# pc_max86150_breakout_qwiic_v1_3.net
KiCad netlist of a schematic drawn in EAGLE
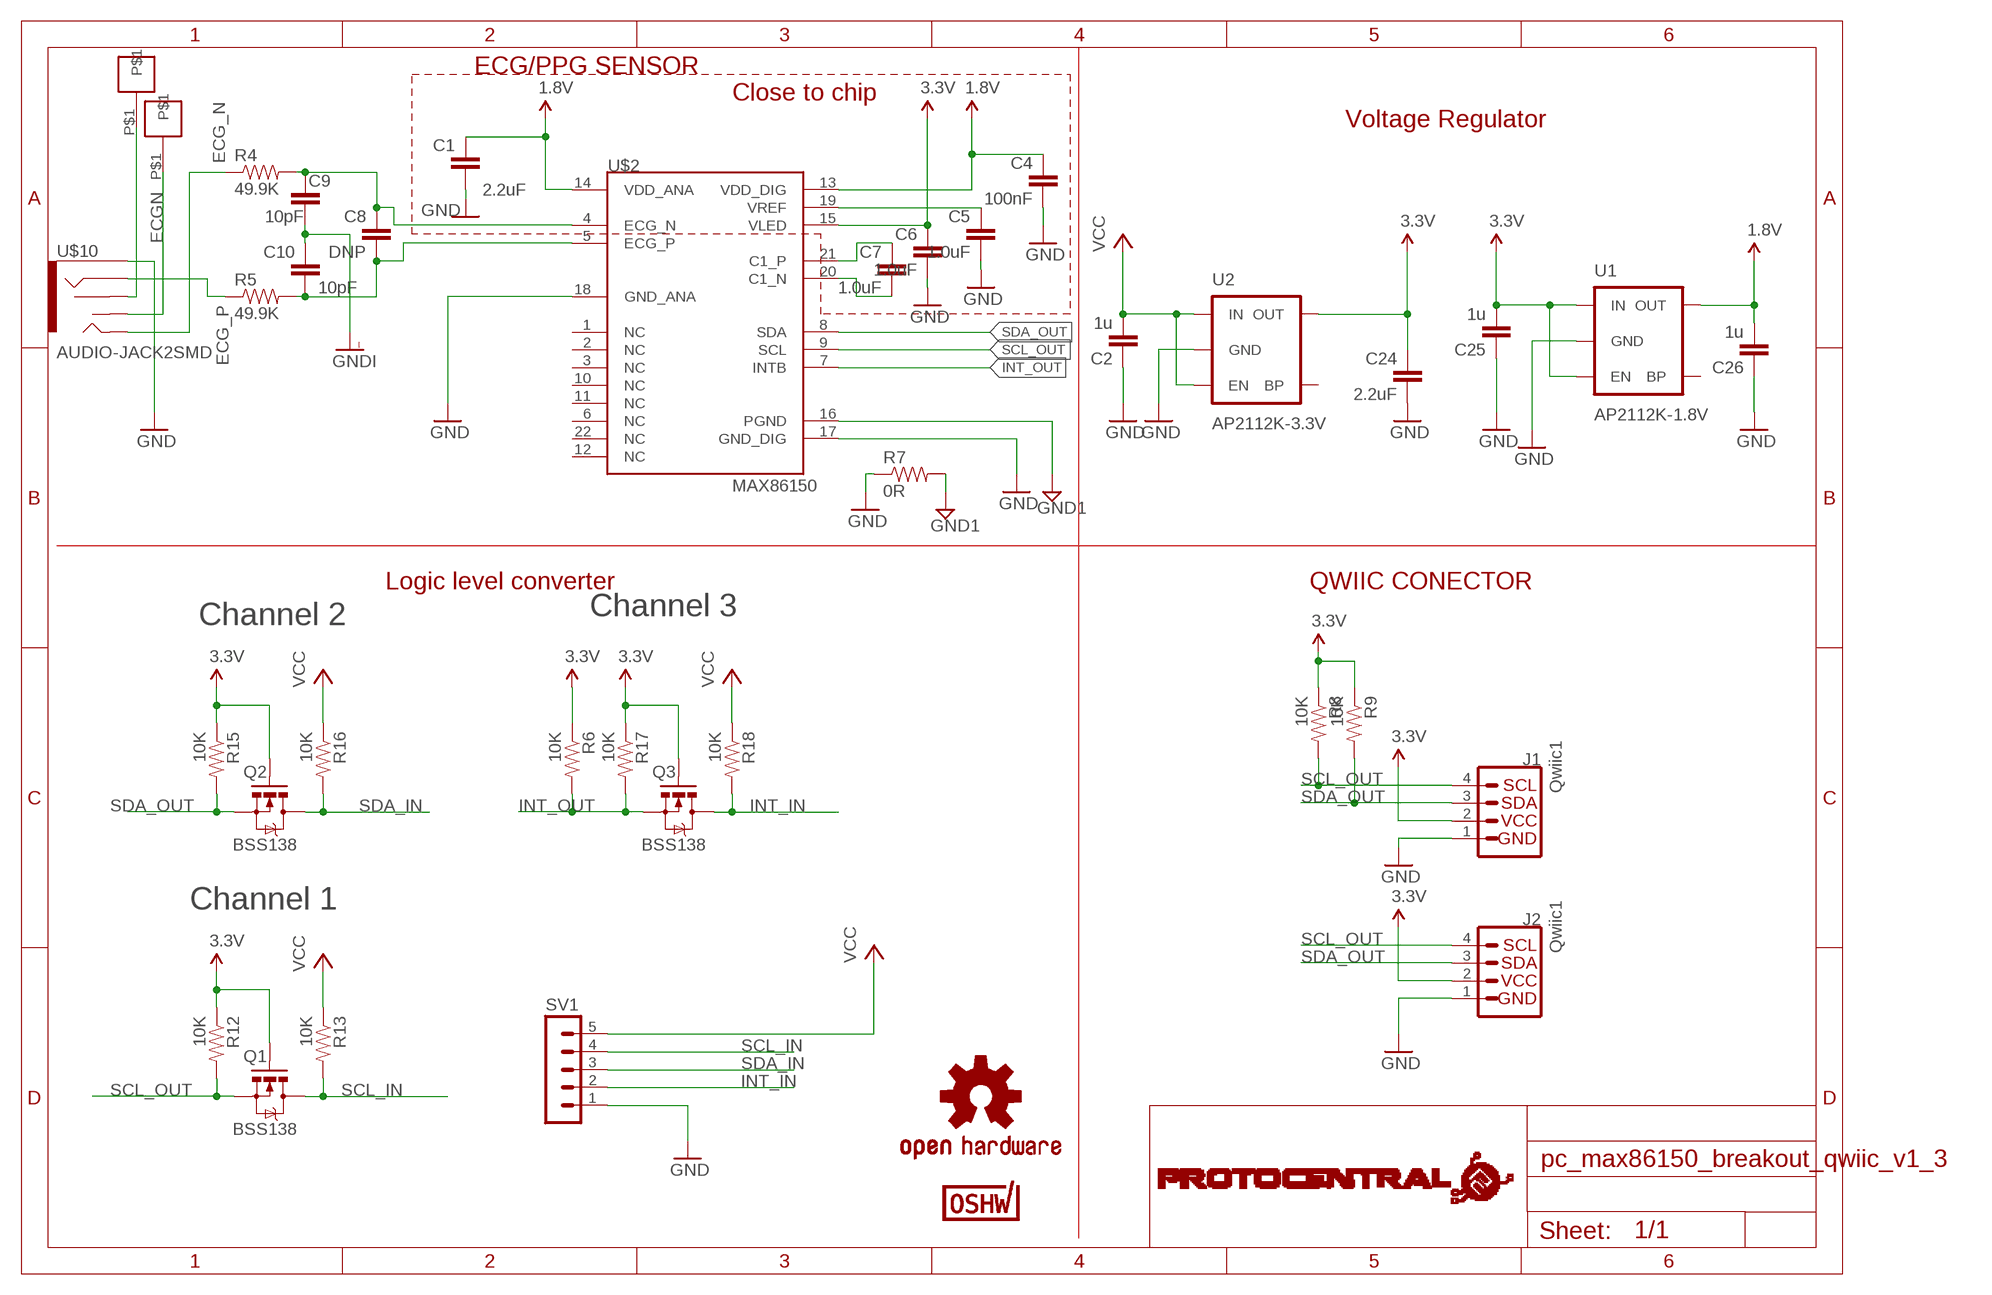
[diagram p0: schematic, sheet 1]

(export (version "E")
  (design (tool "Eeschema 10.0.6"))
  (components
    (comp (ref "C1")
      (value "2.2uF")
      (footprint "eagle-import:0402")
      (libsource (lib "eagle-import") (part "1.0UF-0402-16V-10%"))
    )
    (comp (ref "C2")
      (value "1u")
      (footprint "eagle-import:C0402")
      (libsource (lib "eagle-import") (part "C-EUC0402"))
    )
    (comp (ref "C4")
      (value "100nF")
      (footprint "eagle-import:0402")
      (libsource (lib "eagle-import") (part "1.0UF-0402-16V-10%"))
    )
    (comp (ref "C5")
      (value "1.0uF")
      (footprint "eagle-import:0402")
      (libsource (lib "eagle-import") (part "1.0UF-0402-16V-10%"))
    )
    (comp (ref "C6")
      (value "1.0uF")
      (footprint "eagle-import:0402")
      (libsource (lib "eagle-import") (part "1.0UF-0402-16V-10%"))
    )
    (comp (ref "C7")
      (value "1.0uF")
      (footprint "eagle-import:0402")
      (libsource (lib "eagle-import") (part "1.0UF-0402-16V-10%"))
    )
    (comp (ref "C8")
      (value "DNP")
      (footprint "eagle-import:0402")
      (libsource (lib "eagle-import") (part "1.0UF-0402-16V-10%"))
    )
    (comp (ref "C9")
      (value "10pF")
      (footprint "eagle-import:0402")
      (libsource (lib "eagle-import") (part "1.0UF-0402-16V-10%"))
    )
    (comp (ref "C10")
      (value "10pF")
      (footprint "eagle-import:0402")
      (libsource (lib "eagle-import") (part "1.0UF-0402-16V-10%"))
    )
    (comp (ref "C24")
      (value "2.2uF")
      (footprint "eagle-import:C0402")
      (libsource (lib "eagle-import") (part "C-EUC0402"))
    )
    (comp (ref "C25")
      (value "1u")
      (footprint "eagle-import:C0402")
      (libsource (lib "eagle-import") (part "C-EUC0402"))
    )
    (comp (ref "C26")
      (value "1u")
      (footprint "eagle-import:C0402")
      (libsource (lib "eagle-import") (part "C-EUC0402"))
    )
    (comp (ref "J1")
      (value "Qwiic1")
      (footprint "eagle-import:1X04_1MM_RA")
      (libsource (lib "eagle-import") (part "QWIIC_CONNECTORJS-1MM"))
    )
    (comp (ref "J2")
      (value "Qwiic1")
      (footprint "eagle-import:1X04_1MM_RA")
      (libsource (lib "eagle-import") (part "QWIIC_CONNECTORJS-1MM"))
    )
    (comp (ref "Q1")
      (value "BSS138")
      (footprint "eagle-import:SOT23-3")
      (libsource (lib "eagle-import") (part "MOSFET-NCHANNELSMD"))
    )
    (comp (ref "Q2")
      (value "BSS138")
      (footprint "eagle-import:SOT23-3")
      (libsource (lib "eagle-import") (part "MOSFET-NCHANNELSMD"))
    )
    (comp (ref "Q3")
      (value "BSS138")
      (footprint "eagle-import:SOT23-3")
      (libsource (lib "eagle-import") (part "MOSFET-NCHANNELSMD"))
    )
    (comp (ref "R4")
      (value "49.9K")
      (footprint "eagle-import:0402-RES")
      (libsource (lib "eagle-import") (part "RESISTOR0402-RES"))
    )
    (comp (ref "R5")
      (value "49.9K")
      (footprint "eagle-import:0402-RES")
      (libsource (lib "eagle-import") (part "RESISTOR0402-RES"))
    )
    (comp (ref "R6")
      (value "10K")
      (footprint "eagle-import:0402-RES")
      (libsource (lib "eagle-import") (part "RESISTOR0402-RES"))
    )
    (comp (ref "R7")
      (value "0R")
      (footprint "eagle-import:0402-RES")
      (libsource (lib "eagle-import") (part "RESISTOR0402-RES"))
    )
    (comp (ref "R8")
      (value "10K")
      (footprint "eagle-import:0402-RES")
      (libsource (lib "eagle-import") (part "RESISTOR0402-RES"))
    )
    (comp (ref "R9")
      (value "10K")
      (footprint "eagle-import:0402-RES")
      (libsource (lib "eagle-import") (part "RESISTOR0402-RES"))
    )
    (comp (ref "R12")
      (value "10K")
      (footprint "eagle-import:0402-RES")
      (libsource (lib "eagle-import") (part "RESISTOR0402-RES"))
    )
    (comp (ref "R13")
      (value "10K")
      (footprint "eagle-import:0402-RES")
      (libsource (lib "eagle-import") (part "RESISTOR0402-RES"))
    )
    (comp (ref "R15")
      (value "10K")
      (footprint "eagle-import:0402-RES")
      (libsource (lib "eagle-import") (part "RESISTOR0402-RES"))
    )
    (comp (ref "R16")
      (value "10K")
      (footprint "eagle-import:0402-RES")
      (libsource (lib "eagle-import") (part "RESISTOR0402-RES"))
    )
    (comp (ref "R17")
      (value "10K")
      (footprint "eagle-import:0402-RES")
      (libsource (lib "eagle-import") (part "RESISTOR0402-RES"))
    )
    (comp (ref "R18")
      (value "10K")
      (footprint "eagle-import:0402-RES")
      (libsource (lib "eagle-import") (part "RESISTOR0402-RES"))
    )
    (comp (ref "SV1")
      (value "MA05-1")
      (footprint "eagle-import:MA05-1")
      (libsource (lib "eagle-import") (part "MA05-1"))
    )
    (comp (ref "U$2")
      (value "MAX86150")
      (footprint "eagle-import:MAX86150")
      (libsource (lib "eagle-import") (part "MAX86150"))
    )
    (comp (ref "U$3")
      (value "PROTY_LOGO_WITH_TEXT")
      (footprint "eagle-import:PROTY_WITH_TEXT")
      (libsource (lib "eagle-import") (part "PROTY_LOGO_WITH_TEXT"))
    )
    (comp (ref "U$4")
      (value "ECG_PAD")
      (footprint "eagle-import:ECG_PAD1")
      (libsource (lib "eagle-import") (part "ECG_PAD"))
    )
    (comp (ref "U$10")
      (value "AUDIO-JACK2SMD")
      (footprint "eagle-import:AUDIO-JACK-3.5MM-SMD")
      (libsource (lib "eagle-import") (part "AUDIO-JACK2SMD"))
    )
    (comp (ref "U$12")
      (value "OSHW-LOGOM")
      (footprint "eagle-import:OSHW-LOGO-M")
      (libsource (lib "eagle-import") (part "OSHW-LOGOM"))
    )
    (comp (ref "U$13")
      (value "ECG_PAD")
      (footprint "eagle-import:ECG_PAD1")
      (libsource (lib "eagle-import") (part "ECG_PAD"))
    )
    (comp (ref "U$17")
      (value "CERT-SMALL")
      (footprint "eagle-import:CERT-SMALL-SILK")
      (libsource (lib "eagle-import") (part "CERT-SMALL"))
    )
    (comp (ref "U1")
      (value "AP2112K-1.8V")
      (footprint "eagle-import:SOT23-5")
      (libsource (lib "eagle-import") (part "V_REG_LDOSMD"))
    )
    (comp (ref "U2")
      (value "AP2112K-3.3V")
      (footprint "eagle-import:SOT23-5")
      (libsource (lib "eagle-import") (part "V_REG_LDOSMD"))
    )
  )
  (nets
    (net (code "1") (name "/ECGN") (class "Default")
      (node (ref "U$10") (pin "TSH") (pinfunction "TSH_TSH") (pintype "bidirectional"))
      (node (ref "U$13") (pin "P$1") (pinfunction "P$1_P$1") (pintype "bidirectional"))
    )
    (net (code "2") (name "/ECG_N") (class "Default")
      (node (ref "R4") (pin "1") (pinfunction "1_1") (pintype "passive"))
      (node (ref "U$10") (pin "TIP") (pinfunction "TIP_TIP") (pintype "bidirectional"))
    )
    (net (code "3") (name "/ECG_P") (class "Default")
      (node (ref "R5") (pin "1") (pinfunction "1_1") (pintype "passive"))
      (node (ref "U$10") (pin "RING") (pinfunction "RING_RING") (pintype "bidirectional"))
    )
    (net (code "4") (name "/INT_IN") (class "Default")
      (node (ref "Q3") (pin "3") (pinfunction "D_3") (pintype "passive"))
      (node (ref "R18") (pin "2") (pinfunction "2_2") (pintype "passive"))
      (node (ref "SV1") (pin "2") (pinfunction "2_2") (pintype "passive"))
    )
    (net (code "5") (name "/SCL_IN") (class "Default")
      (node (ref "Q1") (pin "3") (pinfunction "D_3") (pintype "passive"))
      (node (ref "R13") (pin "2") (pinfunction "2_2") (pintype "passive"))
      (node (ref "SV1") (pin "4") (pinfunction "4_4") (pintype "passive"))
    )
    (net (code "6") (name "/SDA_IN") (class "Default")
      (node (ref "Q2") (pin "3") (pinfunction "D_3") (pintype "passive"))
      (node (ref "R16") (pin "2") (pinfunction "2_2") (pintype "passive"))
      (node (ref "SV1") (pin "3") (pinfunction "3_3") (pintype "passive"))
    )
    (net (code "7") (name "1.8V") (class "Default")
      (node (ref "C1") (pin "1") (pinfunction "1_1") (pintype "passive"))
      (node (ref "C26") (pin "2") (pinfunction "2_2") (pintype "passive"))
      (node (ref "C4") (pin "1") (pinfunction "1_1") (pintype "passive"))
      (node (ref "U$2") (pin "13") (pinfunction "VDD_DIG_13") (pintype "bidirectional"))
      (node (ref "U$2") (pin "14") (pinfunction "VDD_ANA_14") (pintype "bidirectional"))
      (node (ref "U1") (pin "5") (pinfunction "OUT_5") (pintype "passive"))
    )
    (net (code "8") (name "3.3V") (class "Default")
      (node (ref "C24") (pin "1") (pinfunction "1_1") (pintype "passive"))
      (node (ref "C25") (pin "2") (pinfunction "2_2") (pintype "passive"))
      (node (ref "C6") (pin "1") (pinfunction "1_1") (pintype "passive"))
      (node (ref "J1") (pin "2") (pinfunction "2_2") (pintype "power_in"))
      (node (ref "J2") (pin "2") (pinfunction "2_2") (pintype "power_in"))
      (node (ref "Q1") (pin "1") (pinfunction "G_1") (pintype "passive"))
      (node (ref "Q2") (pin "1") (pinfunction "G_1") (pintype "passive"))
      (node (ref "Q3") (pin "1") (pinfunction "G_1") (pintype "passive"))
      (node (ref "R12") (pin "1") (pinfunction "1_1") (pintype "passive"))
      (node (ref "R15") (pin "1") (pinfunction "1_1") (pintype "passive"))
      (node (ref "R17") (pin "1") (pinfunction "1_1") (pintype "passive"))
      (node (ref "R6") (pin "1") (pinfunction "1_1") (pintype "passive"))
      (node (ref "R8") (pin "1") (pinfunction "1_1") (pintype "passive"))
      (node (ref "R9") (pin "1") (pinfunction "1_1") (pintype "passive"))
      (node (ref "U$2") (pin "15") (pinfunction "VLED_15") (pintype "bidirectional"))
      (node (ref "U1") (pin "1") (pinfunction "IN_1") (pintype "input"))
      (node (ref "U1") (pin "3") (pinfunction "EN_3") (pintype "input"))
      (node (ref "U2") (pin "5") (pinfunction "OUT_5") (pintype "passive"))
    )
    (net (code "9") (name "GND") (class "Default")
      (node (ref "C1") (pin "2") (pinfunction "2_2") (pintype "passive"))
      (node (ref "C2") (pin "1") (pinfunction "1_1") (pintype "passive"))
      (node (ref "C24") (pin "2") (pinfunction "2_2") (pintype "passive"))
      (node (ref "C25") (pin "1") (pinfunction "1_1") (pintype "passive"))
      (node (ref "C26") (pin "1") (pinfunction "1_1") (pintype "passive"))
      (node (ref "C4") (pin "2") (pinfunction "2_2") (pintype "passive"))
      (node (ref "C5") (pin "2") (pinfunction "2_2") (pintype "passive"))
      (node (ref "C6") (pin "2") (pinfunction "2_2") (pintype "passive"))
      (node (ref "J1") (pin "1") (pinfunction "1_1") (pintype "power_in"))
      (node (ref "J2") (pin "1") (pinfunction "1_1") (pintype "power_in"))
      (node (ref "R7") (pin "1") (pinfunction "1_1") (pintype "passive"))
      (node (ref "SV1") (pin "1") (pinfunction "1_1") (pintype "passive"))
      (node (ref "U$10") (pin "SLEEVE") (pinfunction "SLEEVE_SLEEVE") (pintype "bidirectional"))
      (node (ref "U$2") (pin "17") (pinfunction "GND_DIG_17") (pintype "bidirectional"))
      (node (ref "U$2") (pin "18") (pinfunction "GND_ANA_18") (pintype "bidirectional"))
      (node (ref "U1") (pin "2") (pinfunction "GND_2") (pintype "input"))
      (node (ref "U2") (pin "2") (pinfunction "GND_2") (pintype "input"))
    )
    (net (code "10") (name "GND1") (class "Default")
      (node (ref "R7") (pin "2") (pinfunction "2_2") (pintype "passive"))
      (node (ref "U$2") (pin "16") (pinfunction "PGND_16") (pintype "bidirectional"))
    )
    (net (code "11") (name "GNDI") (class "Default")
      (node (ref "C10") (pin "1") (pinfunction "1_1") (pintype "passive"))
      (node (ref "C9") (pin "2") (pinfunction "2_2") (pintype "passive"))
    )
    (net (code "12") (name "INT_OUT") (class "Default")
      (node (ref "Q3") (pin "2") (pinfunction "S_2") (pintype "passive"))
      (node (ref "R17") (pin "2") (pinfunction "2_2") (pintype "passive"))
      (node (ref "R6") (pin "2") (pinfunction "2_2") (pintype "passive"))
      (node (ref "U$2") (pin "7") (pinfunction "INTB_7") (pintype "bidirectional"))
    )
    (net (code "13") (name "Net-(U$2-C1_N)") (class "Default")
      (node (ref "C7") (pin "2") (pinfunction "2_2") (pintype "passive"))
      (node (ref "U$2") (pin "20") (pinfunction "C1_N_20") (pintype "bidirectional"))
    )
    (net (code "14") (name "Net-(U$2-C1_P)") (class "Default")
      (node (ref "C7") (pin "1") (pinfunction "1_1") (pintype "passive"))
      (node (ref "U$2") (pin "21") (pinfunction "C1_P_21") (pintype "bidirectional"))
    )
    (net (code "15") (name "Net-(U$2-ECG_N)") (class "Default")
      (node (ref "C8") (pin "1") (pinfunction "1_1") (pintype "passive"))
      (node (ref "C9") (pin "1") (pinfunction "1_1") (pintype "passive"))
      (node (ref "R4") (pin "2") (pinfunction "2_2") (pintype "passive"))
      (node (ref "U$2") (pin "4") (pinfunction "ECG_N_4") (pintype "bidirectional"))
    )
    (net (code "16") (name "Net-(U$2-ECG_P)") (class "Default")
      (node (ref "C10") (pin "2") (pinfunction "2_2") (pintype "passive"))
      (node (ref "C8") (pin "2") (pinfunction "2_2") (pintype "passive"))
      (node (ref "R5") (pin "2") (pinfunction "2_2") (pintype "passive"))
      (node (ref "U$2") (pin "5") (pinfunction "ECG_P_5") (pintype "bidirectional"))
    )
    (net (code "17") (name "Net-(U$2-VREF)") (class "Default")
      (node (ref "C5") (pin "1") (pinfunction "1_1") (pintype "passive"))
      (node (ref "U$2") (pin "19") (pinfunction "VREF_19") (pintype "bidirectional"))
    )
    (net (code "18") (name "Net-(U$10-PadRSH)") (class "Default")
      (node (ref "U$10") (pin "RSH") (pinfunction "RSH_RSH") (pintype "bidirectional"))
      (node (ref "U$4") (pin "P$1") (pinfunction "P$1_P$1") (pintype "bidirectional"))
    )
    (net (code "19") (name "SCL_OUT") (class "Default")
      (node (ref "J1") (pin "4") (pinfunction "4_4") (pintype "passive"))
      (node (ref "J2") (pin "4") (pinfunction "4_4") (pintype "passive"))
      (node (ref "Q1") (pin "2") (pinfunction "S_2") (pintype "passive"))
      (node (ref "R12") (pin "2") (pinfunction "2_2") (pintype "passive"))
      (node (ref "R8") (pin "2") (pinfunction "2_2") (pintype "passive"))
      (node (ref "U$2") (pin "9") (pinfunction "SCL_9") (pintype "bidirectional"))
    )
    (net (code "20") (name "SDA_OUT") (class "Default")
      (node (ref "J1") (pin "3") (pinfunction "3_3") (pintype "passive"))
      (node (ref "J2") (pin "3") (pinfunction "3_3") (pintype "passive"))
      (node (ref "Q2") (pin "2") (pinfunction "S_2") (pintype "passive"))
      (node (ref "R15") (pin "2") (pinfunction "2_2") (pintype "passive"))
      (node (ref "R9") (pin "2") (pinfunction "2_2") (pintype "passive"))
      (node (ref "U$2") (pin "8") (pinfunction "SDA_8") (pintype "bidirectional"))
    )
    (net (code "21") (name "VCC") (class "Default")
      (node (ref "C2") (pin "2") (pinfunction "2_2") (pintype "passive"))
      (node (ref "R13") (pin "1") (pinfunction "1_1") (pintype "passive"))
      (node (ref "R16") (pin "1") (pinfunction "1_1") (pintype "passive"))
      (node (ref "R18") (pin "1") (pinfunction "1_1") (pintype "passive"))
      (node (ref "SV1") (pin "5") (pinfunction "5_5") (pintype "passive"))
      (node (ref "U2") (pin "1") (pinfunction "IN_1") (pintype "input"))
      (node (ref "U2") (pin "3") (pinfunction "EN_3") (pintype "input"))
    )
    (net (code "22") (name "unconnected-(U$2-NC-Pad1)") (class "Default")
      (node (ref "U$2") (pin "1") (pinfunction "NC_1") (pintype "bidirectional"))
    )
    (net (code "23") (name "unconnected-(U$2-NC-Pad2)") (class "Default")
      (node (ref "U$2") (pin "2") (pinfunction "NC_2") (pintype "bidirectional"))
    )
    (net (code "24") (name "unconnected-(U$2-NC-Pad3)") (class "Default")
      (node (ref "U$2") (pin "3") (pinfunction "NC_3") (pintype "bidirectional"))
    )
    (net (code "25") (name "unconnected-(U$2-NC-Pad6)") (class "Default")
      (node (ref "U$2") (pin "6") (pinfunction "NC_6") (pintype "bidirectional"))
    )
    (net (code "26") (name "unconnected-(U$2-NC-Pad10)") (class "Default")
      (node (ref "U$2") (pin "10") (pinfunction "NC_10") (pintype "bidirectional"))
    )
    (net (code "27") (name "unconnected-(U$2-NC-Pad11)") (class "Default")
      (node (ref "U$2") (pin "11") (pinfunction "NC_11") (pintype "bidirectional"))
    )
    (net (code "28") (name "unconnected-(U$2-NC-Pad12)") (class "Default")
      (node (ref "U$2") (pin "12") (pinfunction "NC_12") (pintype "bidirectional"))
    )
    (net (code "29") (name "unconnected-(U$2-NC-Pad22)") (class "Default")
      (node (ref "U$2") (pin "22") (pinfunction "NC_22") (pintype "bidirectional"))
    )
    (net (code "30") (name "unconnected-(U1-BP-Pad4)") (class "Default")
      (node (ref "U1") (pin "4") (pinfunction "BP_4") (pintype "input"))
    )
    (net (code "31") (name "unconnected-(U2-BP-Pad4)") (class "Default")
      (node (ref "U2") (pin "4") (pinfunction "BP_4") (pintype "input"))
    )
  )
)
